# NixiTubeClock_IN-4.net
KiCad netlist of a schematic drawn in EAGLE
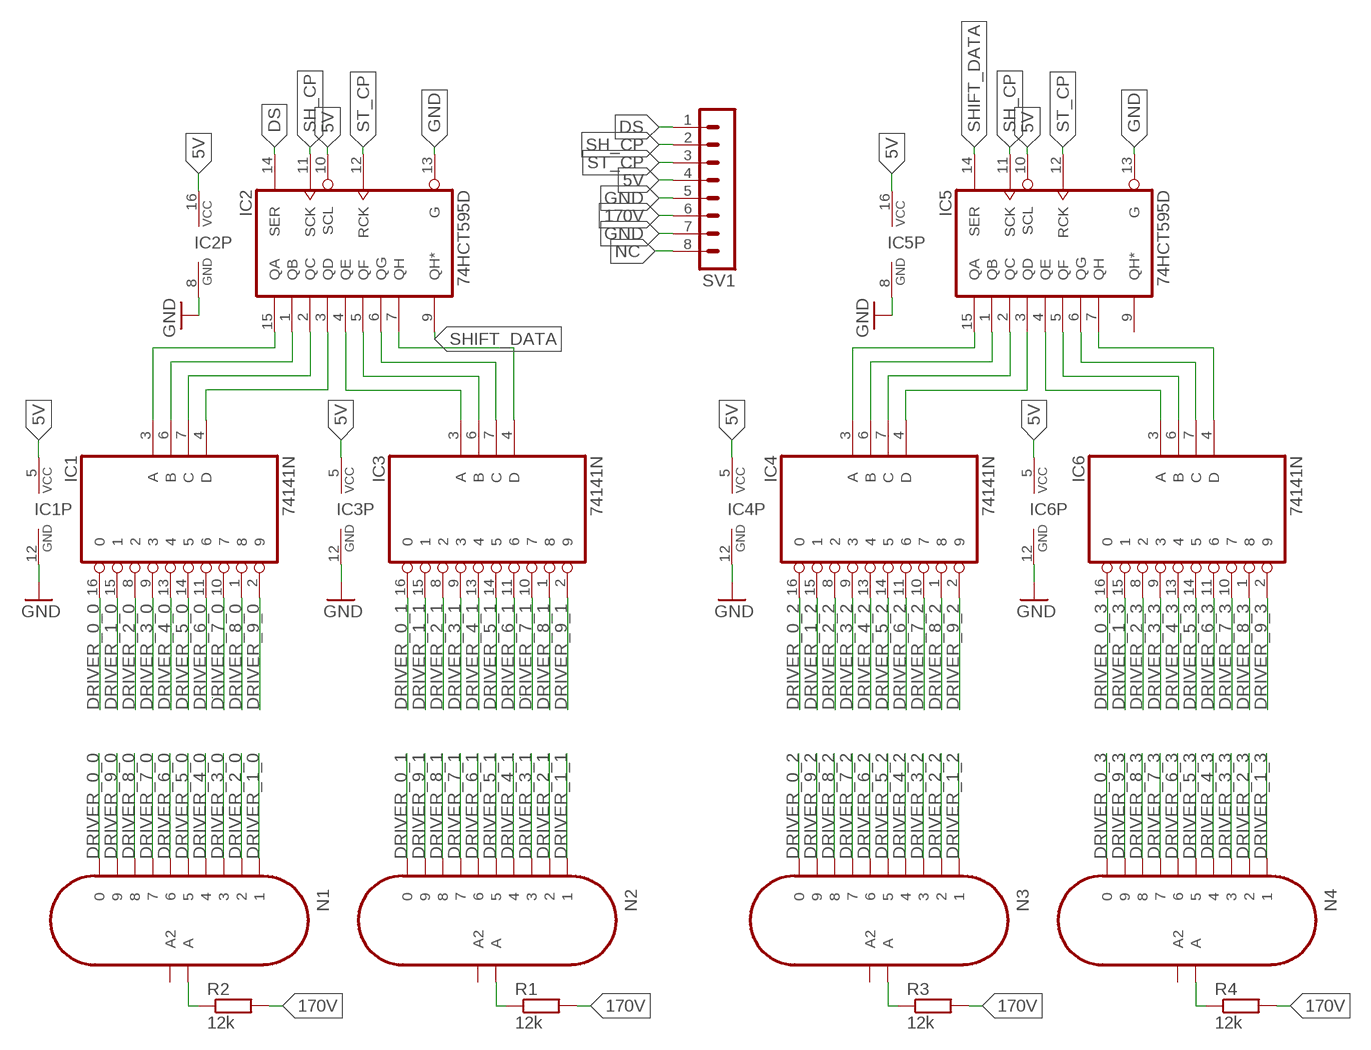
[diagram p0: schematic, sheet 1]
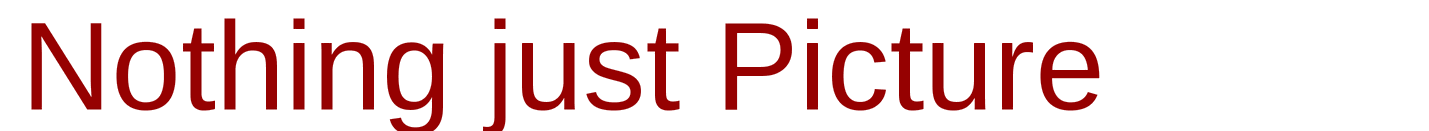
[diagram p1: schematic, sheet 2]

(export (version "E")
  (design (tool "Eeschema 10.0.6"))
  (components
    (comp (ref "IC1")
      (value "74141N")
      (footprint "eagle-import:DIL16")
      (libsource (lib "eagle-import") (part "74141N"))
    )
    (comp (ref "IC2")
      (value "74HCT595D")
      (footprint "eagle-import:SO16")
      (libsource (lib "eagle-import") (part "74595DHCT"))
    )
    (comp (ref "IC3")
      (value "74141N")
      (footprint "eagle-import:DIL16")
      (libsource (lib "eagle-import") (part "74141N"))
    )
    (comp (ref "IC4")
      (value "74141N")
      (footprint "eagle-import:DIL16")
      (libsource (lib "eagle-import") (part "74141N"))
    )
    (comp (ref "IC5")
      (value "74HCT595D")
      (footprint "eagle-import:SO16")
      (libsource (lib "eagle-import") (part "74595DHCT"))
    )
    (comp (ref "IC6")
      (value "74141N")
      (footprint "eagle-import:DIL16")
      (libsource (lib "eagle-import") (part "74141N"))
    )
    (comp (ref "N1")
      (value "IN-4")
      (footprint "eagle-import:IN-18")
      (libsource (lib "eagle-import") (part "IN-4"))
    )
    (comp (ref "N2")
      (value "IN-4")
      (footprint "eagle-import:IN-18")
      (libsource (lib "eagle-import") (part "IN-4"))
    )
    (comp (ref "N3")
      (value "IN-4")
      (footprint "eagle-import:IN-18")
      (libsource (lib "eagle-import") (part "IN-4"))
    )
    (comp (ref "N4")
      (value "IN-4")
      (footprint "eagle-import:IN-18")
      (libsource (lib "eagle-import") (part "IN-4"))
    )
    (comp (ref "R1")
      (value "12k")
      (footprint "eagle-import:R1206")
      (libsource (lib "eagle-import") (part "R-EU_1206R1206"))
    )
    (comp (ref "R2")
      (value "12k")
      (footprint "eagle-import:R1206")
      (libsource (lib "eagle-import") (part "R-EU_1206R1206"))
    )
    (comp (ref "R3")
      (value "12k")
      (footprint "eagle-import:R1206")
      (libsource (lib "eagle-import") (part "R-EU_1206R1206"))
    )
    (comp (ref "R4")
      (value "12k")
      (footprint "eagle-import:R1206")
      (libsource (lib "eagle-import") (part "R-EU_1206R1206"))
    )
    (comp (ref "SV1")
      (value "MA08-1")
      (footprint "eagle-import:MA08-1")
      (libsource (lib "eagle-import") (part "MA08-1"))
    )
  )
  (nets
    (net (code "1") (name "5V") (class "Default")
      (node (ref "IC1") (pin "5") (pinfunction "VCC_5") (pintype "power_in"))
      (node (ref "IC2") (pin "10") (pinfunction "SCL_10") (pintype "input"))
      (node (ref "IC2") (pin "16") (pinfunction "VCC_16") (pintype "power_in"))
      (node (ref "IC3") (pin "5") (pinfunction "VCC_5") (pintype "power_in"))
      (node (ref "IC4") (pin "5") (pinfunction "VCC_5") (pintype "power_in"))
      (node (ref "IC5") (pin "10") (pinfunction "SCL_10") (pintype "input"))
      (node (ref "IC5") (pin "16") (pinfunction "VCC_16") (pintype "power_in"))
      (node (ref "IC6") (pin "5") (pinfunction "VCC_5") (pintype "power_in"))
      (node (ref "SV1") (pin "4") (pinfunction "4_4") (pintype "passive"))
    )
    (net (code "2") (name "170V") (class "Default")
      (node (ref "R1") (pin "2") (pinfunction "2_2") (pintype "passive"))
      (node (ref "R2") (pin "2") (pinfunction "2_2") (pintype "passive"))
      (node (ref "R3") (pin "2") (pinfunction "2_2") (pintype "passive"))
      (node (ref "R4") (pin "2") (pinfunction "2_2") (pintype "passive"))
      (node (ref "SV1") (pin "6") (pinfunction "6_6") (pintype "passive"))
    )
    (net (code "3") (name "DRIVER_0_0") (class "Default")
      (node (ref "IC1") (pin "16") (pinfunction "0_16") (pintype "open_collector"))
      (node (ref "N1") (pin "N/C2") (pinfunction "0_N/C2") (pintype "bidirectional"))
    )
    (net (code "4") (name "DRIVER_0_1") (class "Default")
      (node (ref "IC3") (pin "16") (pinfunction "0_16") (pintype "open_collector"))
      (node (ref "N2") (pin "N/C2") (pinfunction "0_N/C2") (pintype "bidirectional"))
    )
    (net (code "5") (name "DRIVER_0_2") (class "Default")
      (node (ref "IC4") (pin "16") (pinfunction "0_16") (pintype "open_collector"))
      (node (ref "N3") (pin "N/C2") (pinfunction "0_N/C2") (pintype "bidirectional"))
    )
    (net (code "6") (name "DRIVER_0_3") (class "Default")
      (node (ref "IC6") (pin "16") (pinfunction "0_16") (pintype "open_collector"))
      (node (ref "N4") (pin "N/C2") (pinfunction "0_N/C2") (pintype "bidirectional"))
    )
    (net (code "7") (name "DRIVER_1_0") (class "Default")
      (node (ref "IC1") (pin "15") (pinfunction "1_15") (pintype "open_collector"))
      (node (ref "N1") (pin "9") (pinfunction "1_9") (pintype "bidirectional"))
    )
    (net (code "8") (name "DRIVER_1_1") (class "Default")
      (node (ref "IC3") (pin "15") (pinfunction "1_15") (pintype "open_collector"))
      (node (ref "N2") (pin "9") (pinfunction "1_9") (pintype "bidirectional"))
    )
    (net (code "9") (name "DRIVER_1_2") (class "Default")
      (node (ref "IC4") (pin "15") (pinfunction "1_15") (pintype "open_collector"))
      (node (ref "N3") (pin "9") (pinfunction "1_9") (pintype "bidirectional"))
    )
    (net (code "10") (name "DRIVER_1_3") (class "Default")
      (node (ref "IC6") (pin "15") (pinfunction "1_15") (pintype "open_collector"))
      (node (ref "N4") (pin "9") (pinfunction "1_9") (pintype "bidirectional"))
    )
    (net (code "11") (name "DRIVER_2_0") (class "Default")
      (node (ref "IC1") (pin "8") (pinfunction "2_8") (pintype "open_collector"))
      (node (ref "N1") (pin "8") (pinfunction "2_8") (pintype "bidirectional"))
    )
    (net (code "12") (name "DRIVER_2_1") (class "Default")
      (node (ref "IC3") (pin "8") (pinfunction "2_8") (pintype "open_collector"))
      (node (ref "N2") (pin "8") (pinfunction "2_8") (pintype "bidirectional"))
    )
    (net (code "13") (name "DRIVER_2_2") (class "Default")
      (node (ref "IC4") (pin "8") (pinfunction "2_8") (pintype "open_collector"))
      (node (ref "N3") (pin "8") (pinfunction "2_8") (pintype "bidirectional"))
    )
    (net (code "14") (name "DRIVER_2_3") (class "Default")
      (node (ref "IC6") (pin "8") (pinfunction "2_8") (pintype "open_collector"))
      (node (ref "N4") (pin "8") (pinfunction "2_8") (pintype "bidirectional"))
    )
    (net (code "15") (name "DRIVER_3_0") (class "Default")
      (node (ref "IC1") (pin "9") (pinfunction "3_9") (pintype "open_collector"))
      (node (ref "N1") (pin "1") (pinfunction "3_1") (pintype "bidirectional"))
    )
    (net (code "16") (name "DRIVER_3_1") (class "Default")
      (node (ref "IC3") (pin "9") (pinfunction "3_9") (pintype "open_collector"))
      (node (ref "N2") (pin "1") (pinfunction "3_1") (pintype "bidirectional"))
    )
    (net (code "17") (name "DRIVER_3_2") (class "Default")
      (node (ref "IC4") (pin "9") (pinfunction "3_9") (pintype "open_collector"))
      (node (ref "N3") (pin "1") (pinfunction "3_1") (pintype "bidirectional"))
    )
    (net (code "18") (name "DRIVER_3_3") (class "Default")
      (node (ref "IC6") (pin "9") (pinfunction "3_9") (pintype "open_collector"))
      (node (ref "N4") (pin "1") (pinfunction "3_1") (pintype "bidirectional"))
    )
    (net (code "19") (name "DRIVER_4_0") (class "Default")
      (node (ref "IC1") (pin "13") (pinfunction "4_13") (pintype "open_collector"))
      (node (ref "N1") (pin "N/C") (pinfunction "4_N/C") (pintype "bidirectional"))
    )
    (net (code "20") (name "DRIVER_4_1") (class "Default")
      (node (ref "IC3") (pin "13") (pinfunction "4_13") (pintype "open_collector"))
      (node (ref "N2") (pin "N/C") (pinfunction "4_N/C") (pintype "bidirectional"))
    )
    (net (code "21") (name "DRIVER_4_2") (class "Default")
      (node (ref "IC4") (pin "13") (pinfunction "4_13") (pintype "open_collector"))
      (node (ref "N3") (pin "N/C") (pinfunction "4_N/C") (pintype "bidirectional"))
    )
    (net (code "22") (name "DRIVER_4_3") (class "Default")
      (node (ref "IC6") (pin "13") (pinfunction "4_13") (pintype "open_collector"))
      (node (ref "N4") (pin "N/C") (pinfunction "4_N/C") (pintype "bidirectional"))
    )
    (net (code "23") (name "DRIVER_5_0") (class "Default")
      (node (ref "IC1") (pin "14") (pinfunction "5_14") (pintype "open_collector"))
      (node (ref "N1") (pin "A2") (pinfunction "5_A2") (pintype "bidirectional"))
    )
    (net (code "24") (name "DRIVER_5_1") (class "Default")
      (node (ref "IC3") (pin "14") (pinfunction "5_14") (pintype "open_collector"))
      (node (ref "N2") (pin "A2") (pinfunction "5_A2") (pintype "bidirectional"))
    )
    (net (code "25") (name "DRIVER_5_2") (class "Default")
      (node (ref "IC4") (pin "14") (pinfunction "5_14") (pintype "open_collector"))
      (node (ref "N3") (pin "A2") (pinfunction "5_A2") (pintype "bidirectional"))
    )
    (net (code "26") (name "DRIVER_5_3") (class "Default")
      (node (ref "IC6") (pin "14") (pinfunction "5_14") (pintype "open_collector"))
      (node (ref "N4") (pin "A2") (pinfunction "5_A2") (pintype "bidirectional"))
    )
    (net (code "27") (name "DRIVER_6_0") (class "Default")
      (node (ref "IC1") (pin "11") (pinfunction "6_11") (pintype "open_collector"))
      (node (ref "N1") (pin "4") (pinfunction "6_4") (pintype "bidirectional"))
    )
    (net (code "28") (name "DRIVER_6_1") (class "Default")
      (node (ref "IC3") (pin "11") (pinfunction "6_11") (pintype "open_collector"))
      (node (ref "N2") (pin "4") (pinfunction "6_4") (pintype "bidirectional"))
    )
    (net (code "29") (name "DRIVER_6_2") (class "Default")
      (node (ref "IC4") (pin "11") (pinfunction "6_11") (pintype "open_collector"))
      (node (ref "N3") (pin "4") (pinfunction "6_4") (pintype "bidirectional"))
    )
    (net (code "30") (name "DRIVER_6_3") (class "Default")
      (node (ref "IC6") (pin "11") (pinfunction "6_11") (pintype "open_collector"))
      (node (ref "N4") (pin "4") (pinfunction "6_4") (pintype "bidirectional"))
    )
    (net (code "31") (name "DRIVER_7_0") (class "Default")
      (node (ref "IC1") (pin "10") (pinfunction "7_10") (pintype "open_collector"))
      (node (ref "N1") (pin "7") (pinfunction "7_7") (pintype "bidirectional"))
    )
    (net (code "32") (name "DRIVER_7_1") (class "Default")
      (node (ref "IC3") (pin "10") (pinfunction "7_10") (pintype "open_collector"))
      (node (ref "N2") (pin "7") (pinfunction "7_7") (pintype "bidirectional"))
    )
    (net (code "33") (name "DRIVER_7_2") (class "Default")
      (node (ref "IC4") (pin "10") (pinfunction "7_10") (pintype "open_collector"))
      (node (ref "N3") (pin "7") (pinfunction "7_7") (pintype "bidirectional"))
    )
    (net (code "34") (name "DRIVER_7_3") (class "Default")
      (node (ref "IC6") (pin "10") (pinfunction "7_10") (pintype "open_collector"))
      (node (ref "N4") (pin "7") (pinfunction "7_7") (pintype "bidirectional"))
    )
    (net (code "35") (name "DRIVER_8_0") (class "Default")
      (node (ref "IC1") (pin "1") (pinfunction "8_1") (pintype "open_collector"))
      (node (ref "N1") (pin "5") (pinfunction "8_5") (pintype "bidirectional"))
    )
    (net (code "36") (name "DRIVER_8_1") (class "Default")
      (node (ref "IC3") (pin "1") (pinfunction "8_1") (pintype "open_collector"))
      (node (ref "N2") (pin "5") (pinfunction "8_5") (pintype "bidirectional"))
    )
    (net (code "37") (name "DRIVER_8_2") (class "Default")
      (node (ref "IC4") (pin "1") (pinfunction "8_1") (pintype "open_collector"))
      (node (ref "N3") (pin "5") (pinfunction "8_5") (pintype "bidirectional"))
    )
    (net (code "38") (name "DRIVER_8_3") (class "Default")
      (node (ref "IC6") (pin "1") (pinfunction "8_1") (pintype "open_collector"))
      (node (ref "N4") (pin "5") (pinfunction "8_5") (pintype "bidirectional"))
    )
    (net (code "39") (name "DRIVER_9_0") (class "Default")
      (node (ref "IC1") (pin "2") (pinfunction "9_2") (pintype "open_collector"))
      (node (ref "N1") (pin "6") (pinfunction "9_6") (pintype "bidirectional"))
    )
    (net (code "40") (name "DRIVER_9_1") (class "Default")
      (node (ref "IC3") (pin "2") (pinfunction "9_2") (pintype "open_collector"))
      (node (ref "N2") (pin "6") (pinfunction "9_6") (pintype "bidirectional"))
    )
    (net (code "41") (name "DRIVER_9_2") (class "Default")
      (node (ref "IC4") (pin "2") (pinfunction "9_2") (pintype "open_collector"))
      (node (ref "N3") (pin "6") (pinfunction "9_6") (pintype "bidirectional"))
    )
    (net (code "42") (name "DRIVER_9_3") (class "Default")
      (node (ref "IC6") (pin "2") (pinfunction "9_2") (pintype "open_collector"))
      (node (ref "N4") (pin "6") (pinfunction "9_6") (pintype "bidirectional"))
    )
    (net (code "43") (name "DS") (class "Default")
      (node (ref "IC2") (pin "14") (pinfunction "SER_14") (pintype "input"))
      (node (ref "SV1") (pin "1") (pinfunction "1_1") (pintype "passive"))
    )
    (net (code "44") (name "GND") (class "Default")
      (node (ref "IC1") (pin "12") (pinfunction "GND_12") (pintype "power_in"))
      (node (ref "IC2") (pin "13") (pinfunction "G_13") (pintype "input"))
      (node (ref "IC2") (pin "8") (pinfunction "GND_8") (pintype "power_in"))
      (node (ref "IC3") (pin "12") (pinfunction "GND_12") (pintype "power_in"))
      (node (ref "IC4") (pin "12") (pinfunction "GND_12") (pintype "power_in"))
      (node (ref "IC5") (pin "13") (pinfunction "G_13") (pintype "input"))
      (node (ref "IC5") (pin "8") (pinfunction "GND_8") (pintype "power_in"))
      (node (ref "IC6") (pin "12") (pinfunction "GND_12") (pintype "power_in"))
      (node (ref "SV1") (pin "5") (pinfunction "5_5") (pintype "passive"))
      (node (ref "SV1") (pin "7") (pinfunction "7_7") (pintype "passive"))
    )
    (net (code "45") (name "NC") (class "Default")
      (node (ref "SV1") (pin "8") (pinfunction "8_8") (pintype "passive"))
    )
    (net (code "46") (name "Net-(IC1A-A)") (class "Default")
      (node (ref "IC1") (pin "3") (pinfunction "A_3") (pintype "input"))
      (node (ref "IC2") (pin "15") (pinfunction "QA_15") (pintype "tri_state"))
    )
    (net (code "47") (name "Net-(IC1A-B)") (class "Default")
      (node (ref "IC1") (pin "6") (pinfunction "B_6") (pintype "input"))
      (node (ref "IC2") (pin "1") (pinfunction "QB_1") (pintype "tri_state"))
    )
    (net (code "48") (name "Net-(IC1A-C)") (class "Default")
      (node (ref "IC1") (pin "7") (pinfunction "C_7") (pintype "input"))
      (node (ref "IC2") (pin "2") (pinfunction "QC_2") (pintype "tri_state"))
    )
    (net (code "49") (name "Net-(IC1A-D)") (class "Default")
      (node (ref "IC1") (pin "4") (pinfunction "D_4") (pintype "input"))
      (node (ref "IC2") (pin "3") (pinfunction "QD_3") (pintype "tri_state"))
    )
    (net (code "50") (name "Net-(IC2A-QE)") (class "Default")
      (node (ref "IC2") (pin "4") (pinfunction "QE_4") (pintype "tri_state"))
      (node (ref "IC3") (pin "3") (pinfunction "A_3") (pintype "input"))
    )
    (net (code "51") (name "Net-(IC2A-QF)") (class "Default")
      (node (ref "IC2") (pin "5") (pinfunction "QF_5") (pintype "tri_state"))
      (node (ref "IC3") (pin "6") (pinfunction "B_6") (pintype "input"))
    )
    (net (code "52") (name "Net-(IC2A-QG)") (class "Default")
      (node (ref "IC2") (pin "6") (pinfunction "QG_6") (pintype "tri_state"))
      (node (ref "IC3") (pin "7") (pinfunction "C_7") (pintype "input"))
    )
    (net (code "53") (name "Net-(IC2A-QH)") (class "Default")
      (node (ref "IC2") (pin "7") (pinfunction "QH_7") (pintype "tri_state"))
      (node (ref "IC3") (pin "4") (pinfunction "D_4") (pintype "input"))
    )
    (net (code "54") (name "Net-(IC4A-A)") (class "Default")
      (node (ref "IC4") (pin "3") (pinfunction "A_3") (pintype "input"))
      (node (ref "IC5") (pin "15") (pinfunction "QA_15") (pintype "tri_state"))
    )
    (net (code "55") (name "Net-(IC4A-B)") (class "Default")
      (node (ref "IC4") (pin "6") (pinfunction "B_6") (pintype "input"))
      (node (ref "IC5") (pin "1") (pinfunction "QB_1") (pintype "tri_state"))
    )
    (net (code "56") (name "Net-(IC4A-C)") (class "Default")
      (node (ref "IC4") (pin "7") (pinfunction "C_7") (pintype "input"))
      (node (ref "IC5") (pin "2") (pinfunction "QC_2") (pintype "tri_state"))
    )
    (net (code "57") (name "Net-(IC4A-D)") (class "Default")
      (node (ref "IC4") (pin "4") (pinfunction "D_4") (pintype "input"))
      (node (ref "IC5") (pin "3") (pinfunction "QD_3") (pintype "tri_state"))
    )
    (net (code "58") (name "Net-(IC5A-QE)") (class "Default")
      (node (ref "IC5") (pin "4") (pinfunction "QE_4") (pintype "tri_state"))
      (node (ref "IC6") (pin "3") (pinfunction "A_3") (pintype "input"))
    )
    (net (code "59") (name "Net-(IC5A-QF)") (class "Default")
      (node (ref "IC5") (pin "5") (pinfunction "QF_5") (pintype "tri_state"))
      (node (ref "IC6") (pin "6") (pinfunction "B_6") (pintype "input"))
    )
    (net (code "60") (name "Net-(IC5A-QG)") (class "Default")
      (node (ref "IC5") (pin "6") (pinfunction "QG_6") (pintype "tri_state"))
      (node (ref "IC6") (pin "7") (pinfunction "C_7") (pintype "input"))
    )
    (net (code "61") (name "Net-(IC5A-QH)") (class "Default")
      (node (ref "IC5") (pin "7") (pinfunction "QH_7") (pintype "tri_state"))
      (node (ref "IC6") (pin "4") (pinfunction "D_4") (pintype "input"))
    )
    (net (code "62") (name "Net-(N1-A)") (class "Default")
      (node (ref "N1") (pin "0") (pinfunction "A_0") (pintype "bidirectional"))
      (node (ref "R2") (pin "1") (pinfunction "1_1") (pintype "passive"))
    )
    (net (code "63") (name "Net-(N2-A)") (class "Default")
      (node (ref "N2") (pin "0") (pinfunction "A_0") (pintype "bidirectional"))
      (node (ref "R1") (pin "1") (pinfunction "1_1") (pintype "passive"))
    )
    (net (code "64") (name "Net-(N3-A)") (class "Default")
      (node (ref "N3") (pin "0") (pinfunction "A_0") (pintype "bidirectional"))
      (node (ref "R3") (pin "1") (pinfunction "1_1") (pintype "passive"))
    )
    (net (code "65") (name "Net-(N4-A)") (class "Default")
      (node (ref "N4") (pin "0") (pinfunction "A_0") (pintype "bidirectional"))
      (node (ref "R4") (pin "1") (pinfunction "1_1") (pintype "passive"))
    )
    (net (code "66") (name "SHIFT_DATA") (class "Default")
      (node (ref "IC2") (pin "9") (pinfunction "QH*_9") (pintype "tri_state"))
      (node (ref "IC5") (pin "14") (pinfunction "SER_14") (pintype "input"))
    )
    (net (code "67") (name "SH_CP") (class "Default")
      (node (ref "IC2") (pin "11") (pinfunction "SCK_11") (pintype "input"))
      (node (ref "IC5") (pin "11") (pinfunction "SCK_11") (pintype "input"))
      (node (ref "SV1") (pin "2") (pinfunction "2_2") (pintype "passive"))
    )
    (net (code "68") (name "ST_CP") (class "Default")
      (node (ref "IC2") (pin "12") (pinfunction "RCK_12") (pintype "input"))
      (node (ref "IC5") (pin "12") (pinfunction "RCK_12") (pintype "input"))
      (node (ref "SV1") (pin "3") (pinfunction "3_3") (pintype "passive"))
    )
    (net (code "69") (name "unconnected-(IC5A-QH*-Pad9)") (class "Default")
      (node (ref "IC5") (pin "9") (pinfunction "QH*_9") (pintype "tri_state"))
    )
    (net (code "70") (name "unconnected-(N1-A2-Pad2)") (class "Default")
      (node (ref "N1") (pin "2") (pinfunction "A2_2") (pintype "bidirectional"))
    )
    (net (code "71") (name "unconnected-(N2-A2-Pad2)") (class "Default")
      (node (ref "N2") (pin "2") (pinfunction "A2_2") (pintype "bidirectional"))
    )
    (net (code "72") (name "unconnected-(N3-A2-Pad2)") (class "Default")
      (node (ref "N3") (pin "2") (pinfunction "A2_2") (pintype "bidirectional"))
    )
    (net (code "73") (name "unconnected-(N4-A2-Pad2)") (class "Default")
      (node (ref "N4") (pin "2") (pinfunction "A2_2") (pintype "bidirectional"))
    )
  )
)
